# EMI_Filter.net
KiCad netlist of a schematic drawn in Altium Designer
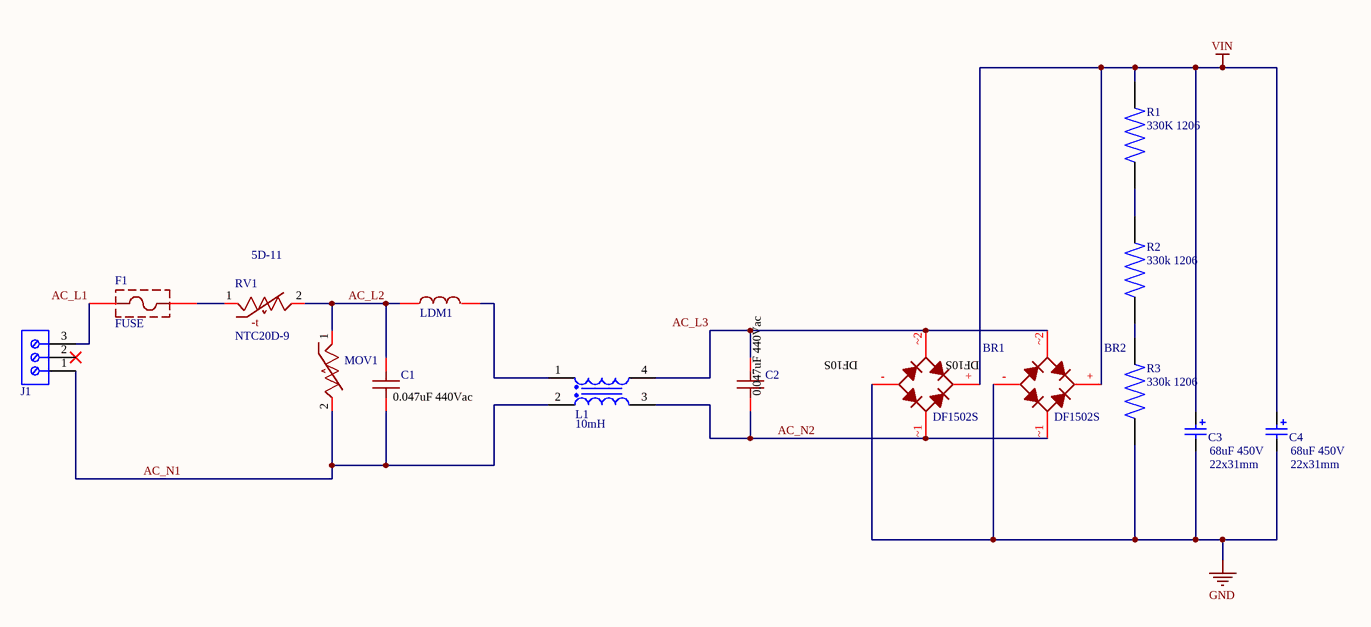
[diagram p0: EMI_Filter.SchDoc]

(export (version "E")
  (design (tool "Eeschema 10.0.6"))
  (components
    (comp (ref "BR1")
      (value "DBLS208GH")
      (footprint "DB SMD")
      (description "Bridge Rectifier Single Phase Standard 1.2 kV Surface Mount DBLS")
      (fields (field (name "MANUFACTURER") "FairchildSemiconductor"))
      (libsource (lib "xEV_Flyback20W") (part "BRIDGE RECT 1.2KV 2A"))
    )
    (comp (ref "BR2")
      (value "DBLS208GH")
      (footprint "DB SMD")
      (description "Bridge Rectifier Single Phase Standard 1.2 kV Surface Mount DBLS")
      (fields (field (name "MANUFACTURER") "FairchildSemiconductor"))
      (libsource (lib "xEV_Flyback20W") (part "BRIDGE RECT 1.2KV 2A"))
    )
    (comp (ref "C1")
      (value "R474I2470CKA2M")
      (footprint "R474I2470CKA2M")
      (description "0.047 µF Film Capacitor 440V 1000V (1kV) Polypropylene (PP), Metallized Radial")
      (fields (field (name "PARAMETER 1") "0.047uF 440Vac") (field (name "TOLERANCE") "20%"))
      (libsource (lib "xEV_Flyback20W") (part "R474I2470CKA2M"))
    )
    (comp (ref "C2")
      (value "R474I2470CKA2M")
      (footprint "R474I2470CKA2M")
      (description "0.047 µF Film Capacitor 440V 1000V (1kV) Polypropylene (PP), Metallized Radial")
      (fields (field (name "PARAMETER 1") "0.047uF 440Vac") (field (name "TOLERANCE") "20%"))
      (libsource (lib "xEV_Flyback20W") (part "R474I2470CKA2M"))
    )
    (comp (ref "C3")
      (value "82uF")
      (footprint "WCAP-AI3H_D22H30")
      (description "WCAP-AI3H Aluminum Electrolytic Capacitor, Snap-In, D22xH30mm, 82uF, 450V")
      (fields
        (field (name "MANUFACTURER") "Wurth Elektronik")
        (field (name "MANUFACTURER PART NUMBER") "861141483002")
      )
      (libsource (lib "Altium_WCAP-AI3H (rev22a)") (part "861141483002"))
    )
    (comp (ref "C4")
      (value "82uF")
      (footprint "WCAP-AI3H_D22H30")
      (description "WCAP-AI3H Aluminum Electrolytic Capacitor, Snap-In, D22xH30mm, 82uF, 450V")
      (fields
        (field (name "MANUFACTURER") "Wurth Elektronik")
        (field (name "MANUFACTURER PART NUMBER") "861141483002")
      )
      (libsource (lib "Altium_WCAP-AI3H (rev22a)") (part "861141483002"))
    )
    (comp (ref "F1")
      (value "FUSE")
      (footprint "FUSE")
      (description "2 A 250 V AC 125 V DC Fuse Board Mount (Cartridge Style)")
      (fields
        (field (name "MANUFACTURER") "Littelfuse")
        (field (name "MANUFACTURER PART NUMBER") "0505025.MXP")
      )
      (libsource (lib "xEV_Flyback20W") (part "FUSE"))
    )
    (comp (ref "J1")
      (value "16A, 300V")
      (footprint "691213710003")
      (description "WR-TBL Series 213 Horizontal Entry Modular, THT, pitch 5mm, 3p")
      (fields
        (field (name "MANUFACTURER PART NUMBER") "691213710003")
        (field (name "MANUFACTURER") "Wurth Elektronik")
      )
      (libsource (lib "Altium_Terminal_Block") (part "691213710003"))
    )
    (comp (ref "L1")
      (value "10mH")
      (footprint "WE-FC_ET20H")
      (description "WE-FC THT Common Mode Power Line Choke, ET20H, 5.9mH, 1.15A, 0.28Ω")
      (fields
        (field (name "MANUFACTURER PART NUMBER") "7448640399")
        (field (name "MANUFACTURER") "Wurth Elektronik")
      )
      (libsource (lib "WE-FC (rev22a)") (part "7448640399"))
    )
    (comp (ref "LDM1")
      (value "SN5-300")
      (footprint "SN5300")
      (description "Filters 25uH 2A DCR=42mOhms")
      (libsource (lib "xEV_Flyback20W") (part "SN5-300"))
    )
    (comp (ref "MOV1")
      (value "MOV-14D751K")
      (footprint "B72214S2271K101")
      (description "750 V 4.5 kA Varistor 1 Circuit Through Hole Disc 14mm")
      (fields (field (name "TOLERANCE") "10%"))
      (libsource (lib "xEV_Flyback20W") (part "MOV-14D751K"))
    )
    (comp (ref "R1")
      (value "330K 1206")
      (footprint "RESC3116X65N")
      (description "13 Ohms Â±5% 0.25W, 1/4W Chip Resistor 1206 (3216 Metric) Moisture Resistant Thick Film")
      (fields (field (name "MP") "RC1206JR-0713RL") (field (name "MF") "Yageo"))
      (libsource (lib "RC1206JR-0713RL (1)") (part "RC1206JR-0713RL"))
    )
    (comp (ref "R2")
      (value "330k 1206")
      (footprint "RESC3116X65N")
      (description "13 Ohms Â±5% 0.25W, 1/4W Chip Resistor 1206 (3216 Metric) Moisture Resistant Thick Film")
      (fields (field (name "MP") "RC1206JR-0713RL") (field (name "MF") "Yageo"))
      (libsource (lib "RC1206JR-0713RL (1)") (part "RC1206JR-0713RL"))
    )
    (comp (ref "R3")
      (value "330k 1206")
      (footprint "RESC3116X65N")
      (description "13 Ohms Â±5% 0.25W, 1/4W Chip Resistor 1206 (3216 Metric) Moisture Resistant Thick Film")
      (fields (field (name "MP") "RC1206JR-0713RL") (field (name "MF") "Yageo"))
      (libsource (lib "RC1206JR-0713RL (1)") (part "RC1206JR-0713RL"))
    )
    (comp (ref "RV1")
      (value "NTC20D-9")
      (footprint "NTC20D9")
      (description "NTC Thermistor 20Ohms DIP 1A 25DegC  20R 9MM")
      (fields (field (name "DIGI-KEY_PART_NUMBER") "495-1441-ND") (field (name "MP") "B72214S2271K101"))
      (libsource (lib "xEV_Flyback20W") (part "NTC20D-9"))
    )
  )
  (nets
    (net (code "1") (name "/AC_L1") (class "Default")
      (node (ref "F1") (pin "1") (pinfunction "1_1") (pintype "passive"))
      (node (ref "J1") (pin "3") (pinfunction "3_3") (pintype "passive"))
    )
    (net (code "2") (name "/AC_L2") (class "Default")
      (node (ref "C1") (pin "1") (pinfunction "1_1") (pintype "passive"))
      (node (ref "LDM1") (pin "1") (pinfunction "1_1") (pintype "passive"))
      (node (ref "MOV1") (pin "1") (pinfunction "1_1") (pintype "passive"))
      (node (ref "RV1") (pin "2") (pinfunction "2_2") (pintype "passive"))
    )
    (net (code "3") (name "/AC_L3") (class "Default")
      (node (ref "BR1") (pin "~2") (pinfunction "~2_~2") (pintype "passive"))
      (node (ref "BR2") (pin "~2") (pinfunction "~2_~2") (pintype "passive"))
      (node (ref "C2") (pin "1") (pinfunction "1_1") (pintype "passive"))
      (node (ref "L1") (pin "4") (pinfunction "4_4") (pintype "passive"))
    )
    (net (code "4") (name "/AC_N1") (class "Default")
      (node (ref "C1") (pin "2") (pinfunction "2_2") (pintype "passive"))
      (node (ref "J1") (pin "1") (pinfunction "1_1") (pintype "passive"))
      (node (ref "L1") (pin "2") (pinfunction "2_2") (pintype "passive"))
      (node (ref "MOV1") (pin "2") (pinfunction "2_2") (pintype "passive"))
    )
    (net (code "5") (name "/AC_N2") (class "Default")
      (node (ref "BR1") (pin "~1") (pinfunction "~1_~1") (pintype "passive"))
      (node (ref "BR2") (pin "~1") (pinfunction "~1_~1") (pintype "passive"))
      (node (ref "C2") (pin "2") (pinfunction "2_2") (pintype "passive"))
      (node (ref "L1") (pin "3") (pinfunction "3_3") (pintype "passive"))
    )
    (net (code "6") (name "GND") (class "Default")
      (node (ref "BR1") (pin "-") (pinfunction "-_-") (pintype "passive"))
      (node (ref "BR2") (pin "-") (pinfunction "-_-") (pintype "passive"))
      (node (ref "C3") (pin "2") (pinfunction "N_2") (pintype "passive"))
      (node (ref "C4") (pin "2") (pinfunction "N_2") (pintype "passive"))
      (node (ref "R3") (pin "1") (pinfunction "1_1") (pintype "passive"))
    )
    (net (code "7") (name "Net-(F1-Pad2)") (class "Default")
      (node (ref "F1") (pin "2") (pinfunction "2_2") (pintype "passive"))
      (node (ref "RV1") (pin "1") (pinfunction "1_1") (pintype "passive"))
    )
    (net (code "8") (name "Net-(L1-Pad1)") (class "Default")
      (node (ref "L1") (pin "1") (pinfunction "1_1") (pintype "passive"))
      (node (ref "LDM1") (pin "2") (pinfunction "2_2") (pintype "passive"))
    )
    (net (code "9") (name "Net-(R1-Pad1)") (class "Default")
      (node (ref "R1") (pin "1") (pinfunction "1_1") (pintype "passive"))
      (node (ref "R2") (pin "2") (pinfunction "2_2") (pintype "passive"))
    )
    (net (code "10") (name "Net-(R2-Pad1)") (class "Default")
      (node (ref "R2") (pin "1") (pinfunction "1_1") (pintype "passive"))
      (node (ref "R3") (pin "2") (pinfunction "2_2") (pintype "passive"))
    )
    (net (code "11") (name "VIN") (class "Default")
      (node (ref "BR1") (pin "+") (pinfunction "+_+") (pintype "passive"))
      (node (ref "BR2") (pin "+") (pinfunction "+_+") (pintype "passive"))
      (node (ref "C3") (pin "1") (pinfunction "P_1") (pintype "passive"))
      (node (ref "C4") (pin "1") (pinfunction "P_1") (pintype "passive"))
      (node (ref "R1") (pin "2") (pinfunction "2_2") (pintype "passive"))
    )
    (net (code "12") (name "unconnected-(J1-Pad2)") (class "Default")
      (node (ref "J1") (pin "2") (pinfunction "2_2") (pintype "passive+no_connect"))
    )
  )
)
